# CATS-GS-USB.net
KiCad netlist of a schematic drawn in Altium Designer
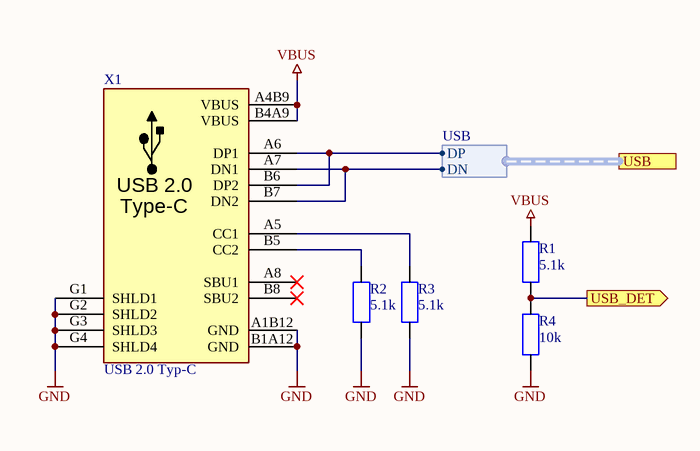
[diagram p0: CATS-GS-USB.SchDoc]

(export (version "E")
  (design (tool "Eeschema 10.0.6"))
  (components
    (comp (ref "R1")
      (value "5.1k")
      (footprint "SMD Widerstand 0402")
      (description "SMD Chip Resistor E24")
      (libsource (lib "") (part "E24 - 5.1k_1"))
    )
    (comp (ref "R2")
      (value "5.1k")
      (footprint "SMD Widerstand 0402")
      (description "SMD Chip Resistor E24")
      (libsource (lib "CATS-EUROC") (part "E24 - 5.1k"))
    )
    (comp (ref "R3")
      (value "5.1k")
      (footprint "SMD Widerstand 0402")
      (description "SMD Chip Resistor E24")
      (libsource (lib "CATS-EUROC") (part "E24 - 5.1k"))
    )
    (comp (ref "R4")
      (value "10k")
      (footprint "SMD Widerstand 0402")
      (description "SMD Chip Resistor E24")
      (libsource (lib "CATS-EUROC") (part "E24 - 10k"))
    )
    (comp (ref "X1")
      (value "USB 2.0 Typ-C")
      (footprint "THT USB-C Socket (A40-00119)")
      (description "Typ-C")
      (libsource (lib "CATS-EUROC") (part "USB Type-C USB 2.0"))
    )
  )
  (nets
    (net (code "2") (name "/USB_DET") (class "Default")
      (node (ref "R1") (pin "2") (pinfunction "2_2") (pintype "passive"))
      (node (ref "R4") (pin "1") (pinfunction "1_1") (pintype "passive"))
    )
    (net (code "4") (name "GND") (class "Default")
      (node (ref "R2") (pin "1") (pinfunction "1_1") (pintype "passive"))
      (node (ref "R3") (pin "1") (pinfunction "1_1") (pintype "passive"))
      (node (ref "R4") (pin "2") (pinfunction "2_2") (pintype "passive"))
      (node (ref "X1") (pin "A1B12") (pinfunction "GND_A1B12") (pintype "passive"))
      (node (ref "X1") (pin "B1A12") (pinfunction "GND_B1A12") (pintype "passive"))
      (node (ref "X1") (pin "G1") (pinfunction "SHLD1_G1") (pintype "passive"))
      (node (ref "X1") (pin "G2") (pinfunction "SHLD2_G2") (pintype "passive"))
      (node (ref "X1") (pin "G3") (pinfunction "SHLD3_G3") (pintype "passive"))
      (node (ref "X1") (pin "G4") (pinfunction "SHLD4_G4") (pintype "passive"))
    )
    (net (code "5") (name "Net-(X1-CC1)") (class "Default")
      (node (ref "R3") (pin "2") (pinfunction "2_2") (pintype "passive"))
      (node (ref "X1") (pin "A5") (pinfunction "CC1_A5") (pintype "passive"))
    )
    (net (code "6") (name "Net-(X1-CC2)") (class "Default")
      (node (ref "R2") (pin "2") (pinfunction "2_2") (pintype "passive"))
      (node (ref "X1") (pin "B5") (pinfunction "CC2_B5") (pintype "passive"))
    )
    (net (code "7") (name "Net-(X1-DN1)") (class "Default")
      (node (ref "X1") (pin "A7") (pinfunction "DN1_A7") (pintype "passive"))
      (node (ref "X1") (pin "B7") (pinfunction "DN2_B7") (pintype "passive"))
    )
    (net (code "8") (name "Net-(X1-DP1)") (class "Default")
      (node (ref "X1") (pin "A6") (pinfunction "DP1_A6") (pintype "passive"))
      (node (ref "X1") (pin "B6") (pinfunction "DP2_B6") (pintype "passive"))
    )
    (net (code "9") (name "VBUS") (class "Default")
      (node (ref "R1") (pin "1") (pinfunction "1_1") (pintype "passive"))
      (node (ref "X1") (pin "A4B9") (pinfunction "VBUS_A4B9") (pintype "passive"))
      (node (ref "X1") (pin "B4A9") (pinfunction "VBUS_B4A9") (pintype "passive"))
    )
    (net (code "10") (name "unconnected-(X1-SBU1-PadA8)") (class "Default")
      (node (ref "X1") (pin "A8") (pinfunction "SBU1_A8") (pintype "passive+no_connect"))
    )
    (net (code "11") (name "unconnected-(X1-SBU2-PadB8)") (class "Default")
      (node (ref "X1") (pin "B8") (pinfunction "SBU2_B8") (pintype "passive+no_connect"))
    )
  )
)
